# shield-ssr-display.net
KiCad netlist of a schematic drawn in EAGLE
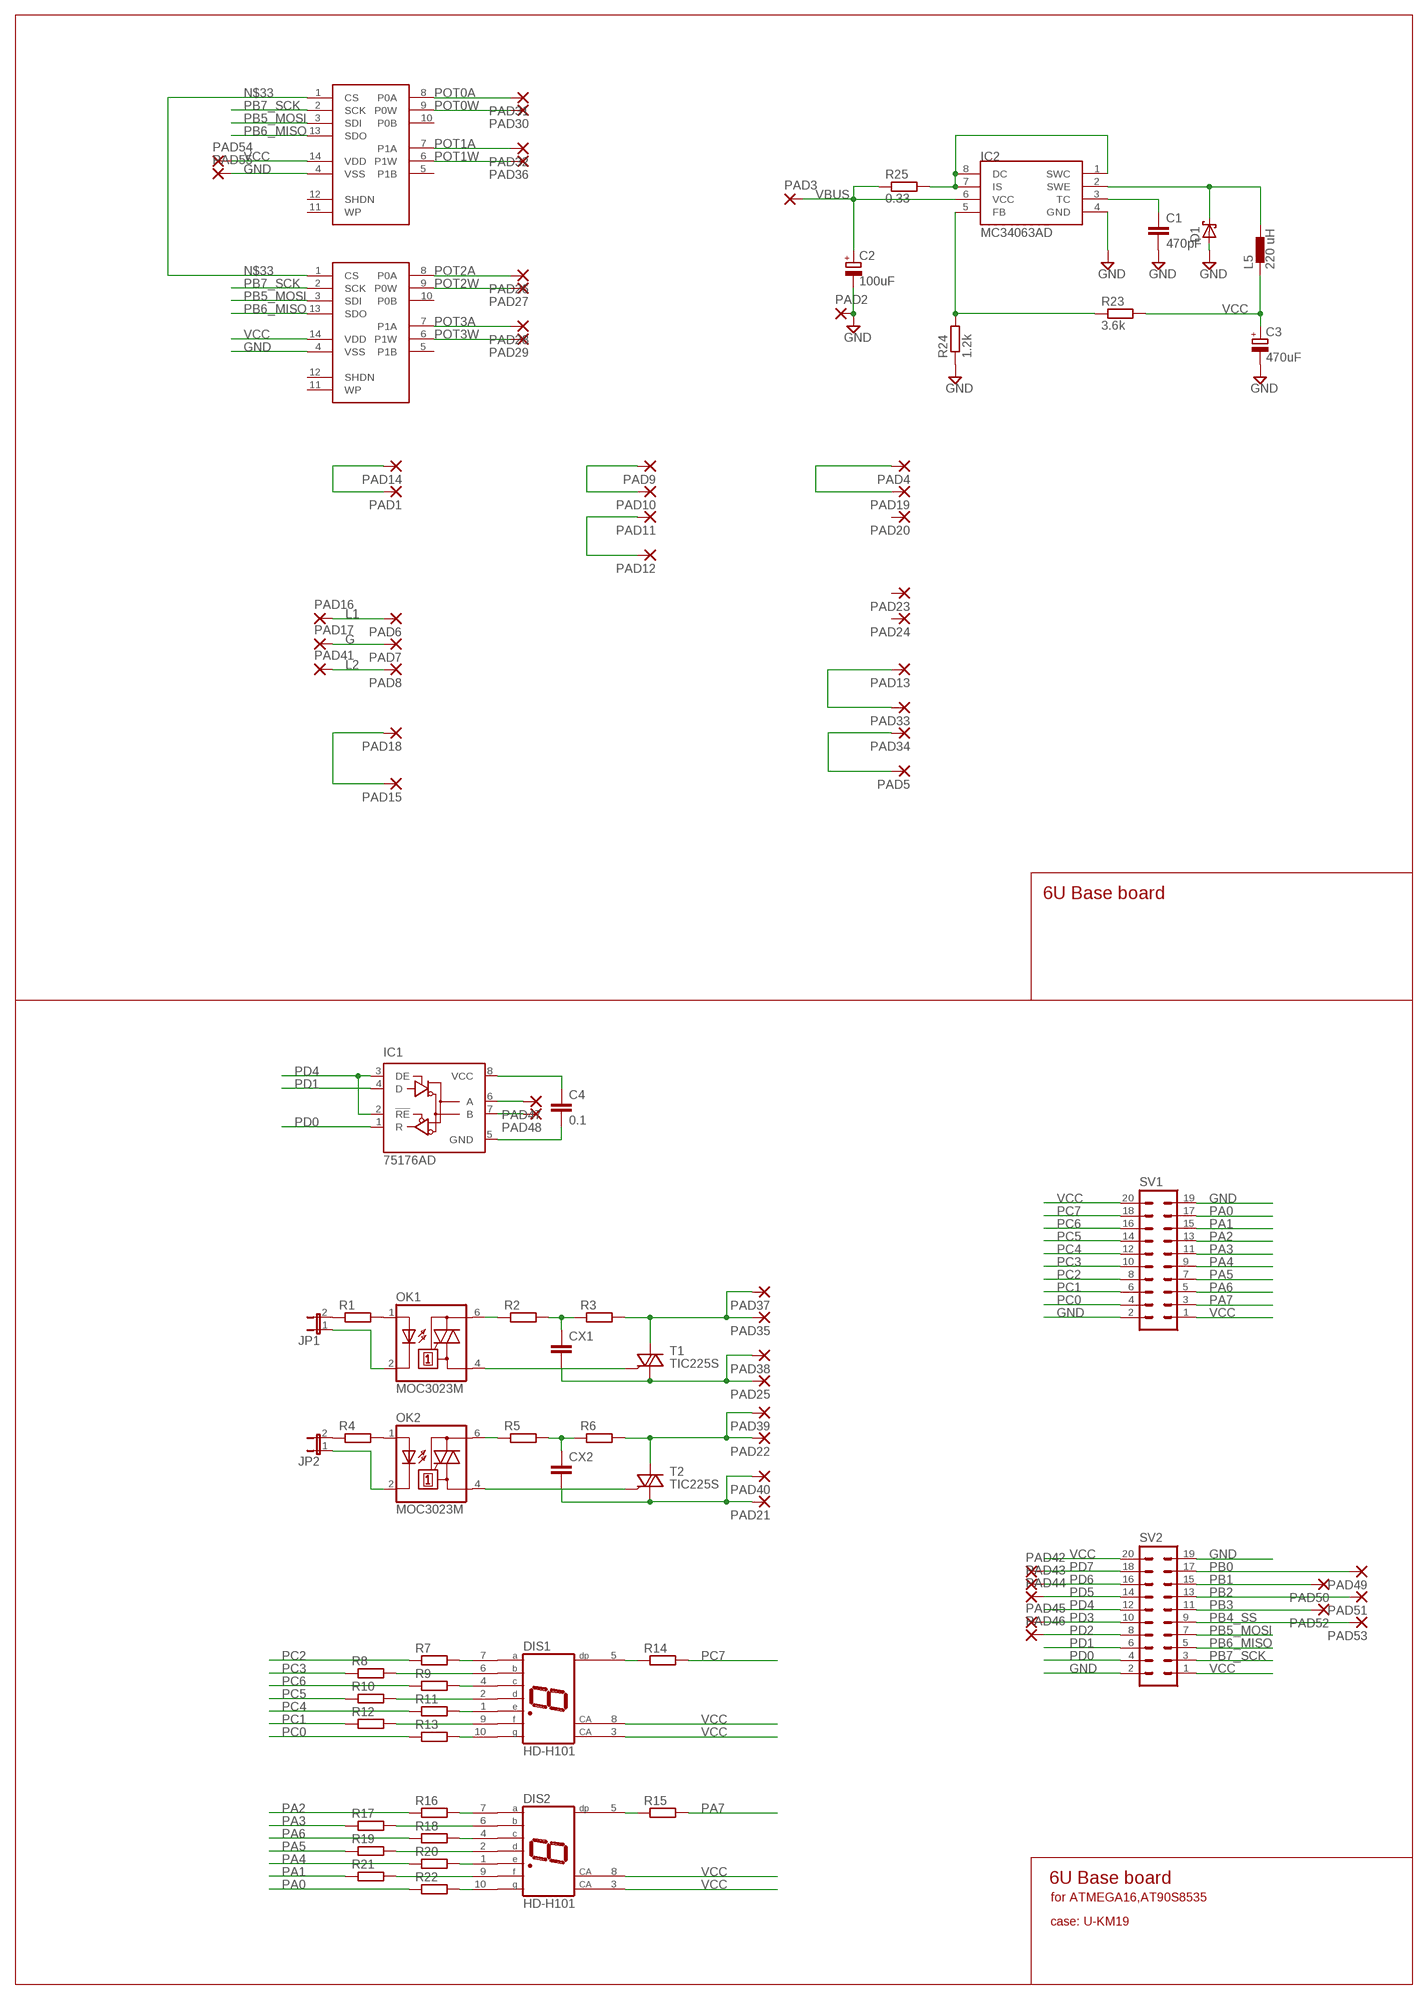
[diagram p0: schematic, sheet 1]

(export (version "E")
  (design (tool "Eeschema 10.0.6"))
  (components
    (comp (ref "C1")
      (value "470pF")
      (footprint "eagle-import:C0805")
      (libsource (lib "eagle-import") (part "C-EUC0805"))
    )
    (comp (ref "C2")
      (value "100uF")
      (footprint "eagle-import:E3,5-8")
      (libsource (lib "eagle-import") (part "CPOL-EUE3.5-8"))
    )
    (comp (ref "C3")
      (value "470uF")
      (footprint "eagle-import:E3,5-8")
      (libsource (lib "eagle-import") (part "CPOL-EUE3.5-8"))
    )
    (comp (ref "C4")
      (value "0.1")
      (footprint "eagle-import:C0805")
      (libsource (lib "eagle-import") (part "C-EUC0805"))
    )
    (comp (ref "CX1")
      (value "CXXC15B5")
      (footprint "eagle-import:XC15B5")
      (libsource (lib "eagle-import") (part "CXXC15B5"))
    )
    (comp (ref "CX2")
      (value "CXXC15B5")
      (footprint "eagle-import:XC15B5")
      (libsource (lib "eagle-import") (part "CXXC15B5"))
    )
    (comp (ref "D1")
      (value "SCHOTTKY-DIODESMD")
      (footprint "eagle-import:SMB")
      (libsource (lib "eagle-import") (part "SCHOTTKY-DIODESMD"))
    )
    (comp (ref "DIS1")
      (value "HD-H101")
      (footprint "eagle-import:HDSP-M")
      (libsource (lib "eagle-import") (part "HD-H101"))
    )
    (comp (ref "DIS2")
      (value "HD-H101")
      (footprint "eagle-import:HDSP-M")
      (libsource (lib "eagle-import") (part "HD-H101"))
    )
    (comp (ref "IC1")
      (value "75176AD")
      (footprint "eagle-import:D_R-PDSO-G8")
      (libsource (lib "eagle-import") (part "75176AD"))
    )
    (comp (ref "IC2")
      (value "MC34063AD")
      (footprint "eagle-import:SOIC8")
      (libsource (lib "eagle-import") (part "MC34063AD"))
    )
    (comp (ref "JP1")
      (value "JP1E")
      (footprint "eagle-import:JP1")
      (libsource (lib "eagle-import") (part "JP1E"))
    )
    (comp (ref "JP2")
      (value "JP1E")
      (footprint "eagle-import:JP1")
      (libsource (lib "eagle-import") (part "JP1E"))
    )
    (comp (ref "L5")
      (value "220 uH")
      (footprint "eagle-import:DR1030")
      (libsource (lib "eagle-import") (part "DR1030"))
    )
    (comp (ref "OK1")
      (value "MOC3023M")
      (footprint "eagle-import:DIL06")
      (fields (field (name "MF") "FAIRCHILD SEMICONDUCTOR") (field (name "MPN") "MOC3023-M"))
      (libsource (lib "eagle-import") (part "MOC30M23"))
    )
    (comp (ref "OK2")
      (value "MOC3023M")
      (footprint "eagle-import:DIL06")
      (fields (field (name "MF") "FAIRCHILD SEMICONDUCTOR") (field (name "MPN") "MOC3023-M"))
      (libsource (lib "eagle-import") (part "MOC30M23"))
    )
    (comp (ref "PAD1")
      (value "2,54/0,8")
      (footprint "eagle-import:2,54_0,8")
      (libsource (lib "eagle-import") (part "2,54/0,8"))
    )
    (comp (ref "PAD2")
      (value "2,54/0,8")
      (footprint "eagle-import:2,54_0,8")
      (libsource (lib "eagle-import") (part "2,54/0,8"))
    )
    (comp (ref "PAD3")
      (value "2,54/0,8")
      (footprint "eagle-import:2,54_0,8")
      (libsource (lib "eagle-import") (part "2,54/0,8"))
    )
    (comp (ref "PAD4")
      (value "2,54/0,8")
      (footprint "eagle-import:2,54_0,8")
      (libsource (lib "eagle-import") (part "2,54/0,8"))
    )
    (comp (ref "PAD5")
      (value "2,54/0,8")
      (footprint "eagle-import:2,54_0,8")
      (libsource (lib "eagle-import") (part "2,54/0,8"))
    )
    (comp (ref "PAD6")
      (value "2,54/0,8")
      (footprint "eagle-import:2,54_0,8")
      (libsource (lib "eagle-import") (part "2,54/0,8"))
    )
    (comp (ref "PAD7")
      (value "2,54/0,8")
      (footprint "eagle-import:2,54_0,8")
      (libsource (lib "eagle-import") (part "2,54/0,8"))
    )
    (comp (ref "PAD8")
      (value "2,54/0,8")
      (footprint "eagle-import:2,54_0,8")
      (libsource (lib "eagle-import") (part "2,54/0,8"))
    )
    (comp (ref "PAD9")
      (value "2,54/0,8")
      (footprint "eagle-import:2,54_0,8")
      (libsource (lib "eagle-import") (part "2,54/0,8"))
    )
    (comp (ref "PAD10")
      (value "2,54/0,8")
      (footprint "eagle-import:2,54_0,8")
      (libsource (lib "eagle-import") (part "2,54/0,8"))
    )
    (comp (ref "PAD11")
      (value "2,54/0,8")
      (footprint "eagle-import:2,54_0,8")
      (libsource (lib "eagle-import") (part "2,54/0,8"))
    )
    (comp (ref "PAD12")
      (value "2,54/0,8")
      (footprint "eagle-import:2,54_0,8")
      (libsource (lib "eagle-import") (part "2,54/0,8"))
    )
    (comp (ref "PAD13")
      (value "2,54/0,8")
      (footprint "eagle-import:2,54_0,8")
      (libsource (lib "eagle-import") (part "2,54/0,8"))
    )
    (comp (ref "PAD14")
      (value "2,54/0,8")
      (footprint "eagle-import:2,54_0,8")
      (libsource (lib "eagle-import") (part "2,54/0,8"))
    )
    (comp (ref "PAD15")
      (value "2,54/0,8")
      (footprint "eagle-import:2,54_0,8")
      (libsource (lib "eagle-import") (part "2,54/0,8"))
    )
    (comp (ref "PAD16")
      (value "2,54/0,8")
      (footprint "eagle-import:2,54_0,8")
      (libsource (lib "eagle-import") (part "2,54/0,8"))
    )
    (comp (ref "PAD17")
      (value "2,54/0,8")
      (footprint "eagle-import:2,54_0,8")
      (libsource (lib "eagle-import") (part "2,54/0,8"))
    )
    (comp (ref "PAD18")
      (value "2,54/0,8")
      (footprint "eagle-import:2,54_0,8")
      (libsource (lib "eagle-import") (part "2,54/0,8"))
    )
    (comp (ref "PAD19")
      (value "2,54/0,8")
      (footprint "eagle-import:2,54_0,8")
      (libsource (lib "eagle-import") (part "2,54/0,8"))
    )
    (comp (ref "PAD20")
      (value "2,54/0,8")
      (footprint "eagle-import:2,54_0,8")
      (libsource (lib "eagle-import") (part "2,54/0,8"))
    )
    (comp (ref "PAD21")
      (value "2,54/0,8")
      (footprint "eagle-import:2,54_0,8")
      (libsource (lib "eagle-import") (part "2,54/0,8"))
    )
    (comp (ref "PAD22")
      (value "2,54/0,8")
      (footprint "eagle-import:2,54_0,8")
      (libsource (lib "eagle-import") (part "2,54/0,8"))
    )
    (comp (ref "PAD23")
      (value "2,54/0,8")
      (footprint "eagle-import:2,54_0,8")
      (libsource (lib "eagle-import") (part "2,54/0,8"))
    )
    (comp (ref "PAD24")
      (value "2,54/0,8")
      (footprint "eagle-import:2,54_0,8")
      (libsource (lib "eagle-import") (part "2,54/0,8"))
    )
    (comp (ref "PAD25")
      (value "2,54/0,8")
      (footprint "eagle-import:2,54_0,8")
      (libsource (lib "eagle-import") (part "2,54/0,8"))
    )
    (comp (ref "PAD26")
      (value "2,54/0,8")
      (footprint "eagle-import:2,54_0,8")
      (libsource (lib "eagle-import") (part "2,54/0,8"))
    )
    (comp (ref "PAD27")
      (value "2,54/0,8")
      (footprint "eagle-import:2,54_0,8")
      (libsource (lib "eagle-import") (part "2,54/0,8"))
    )
    (comp (ref "PAD28")
      (value "2,54/0,8")
      (footprint "eagle-import:2,54_0,8")
      (libsource (lib "eagle-import") (part "2,54/0,8"))
    )
    (comp (ref "PAD29")
      (value "2,54/0,8")
      (footprint "eagle-import:2,54_0,8")
      (libsource (lib "eagle-import") (part "2,54/0,8"))
    )
    (comp (ref "PAD30")
      (value "2,54/0,8")
      (footprint "eagle-import:2,54_0,8")
      (libsource (lib "eagle-import") (part "2,54/0,8"))
    )
    (comp (ref "PAD31")
      (value "2,54/0,8")
      (footprint "eagle-import:2,54_0,8")
      (libsource (lib "eagle-import") (part "2,54/0,8"))
    )
    (comp (ref "PAD32")
      (value "2,54/0,8")
      (footprint "eagle-import:2,54_0,8")
      (libsource (lib "eagle-import") (part "2,54/0,8"))
    )
    (comp (ref "PAD33")
      (value "2,54/0,8")
      (footprint "eagle-import:2,54_0,8")
      (libsource (lib "eagle-import") (part "2,54/0,8"))
    )
    (comp (ref "PAD34")
      (value "2,54/0,8")
      (footprint "eagle-import:2,54_0,8")
      (libsource (lib "eagle-import") (part "2,54/0,8"))
    )
    (comp (ref "PAD35")
      (value "2,54/0,8")
      (footprint "eagle-import:2,54_0,8")
      (libsource (lib "eagle-import") (part "2,54/0,8"))
    )
    (comp (ref "PAD36")
      (value "2,54/0,8")
      (footprint "eagle-import:2,54_0,8")
      (libsource (lib "eagle-import") (part "2,54/0,8"))
    )
    (comp (ref "PAD37")
      (value "2,54/0,8")
      (footprint "eagle-import:2,54_0,8")
      (libsource (lib "eagle-import") (part "2,54/0,8"))
    )
    (comp (ref "PAD38")
      (value "2,54/0,8")
      (footprint "eagle-import:2,54_0,8")
      (libsource (lib "eagle-import") (part "2,54/0,8"))
    )
    (comp (ref "PAD39")
      (value "2,54/0,8")
      (footprint "eagle-import:2,54_0,8")
      (libsource (lib "eagle-import") (part "2,54/0,8"))
    )
    (comp (ref "PAD40")
      (value "2,54/0,8")
      (footprint "eagle-import:2,54_0,8")
      (libsource (lib "eagle-import") (part "2,54/0,8"))
    )
    (comp (ref "PAD41")
      (value "2,54/0,8")
      (footprint "eagle-import:2,54_0,8")
      (libsource (lib "eagle-import") (part "2,54/0,8"))
    )
    (comp (ref "PAD42")
      (value "1,6/0,8")
      (footprint "eagle-import:1,6_0,8")
      (libsource (lib "eagle-import") (part "1,6/0,8"))
    )
    (comp (ref "PAD43")
      (value "1,6/0,8")
      (footprint "eagle-import:1,6_0,8")
      (libsource (lib "eagle-import") (part "1,6/0,8"))
    )
    (comp (ref "PAD44")
      (value "1,6/0,8")
      (footprint "eagle-import:1,6_0,8")
      (libsource (lib "eagle-import") (part "1,6/0,8"))
    )
    (comp (ref "PAD45")
      (value "1,6/0,8")
      (footprint "eagle-import:1,6_0,8")
      (libsource (lib "eagle-import") (part "1,6/0,8"))
    )
    (comp (ref "PAD46")
      (value "1,6/0,8")
      (footprint "eagle-import:1,6_0,8")
      (libsource (lib "eagle-import") (part "1,6/0,8"))
    )
    (comp (ref "PAD47")
      (value "1,6/0,8")
      (footprint "eagle-import:1,6_0,8")
      (libsource (lib "eagle-import") (part "1,6/0,8"))
    )
    (comp (ref "PAD48")
      (value "1,6/0,8")
      (footprint "eagle-import:1,6_0,8")
      (libsource (lib "eagle-import") (part "1,6/0,8"))
    )
    (comp (ref "PAD49")
      (value "1,6/0,8")
      (footprint "eagle-import:1,6_0,8")
      (libsource (lib "eagle-import") (part "1,6/0,8"))
    )
    (comp (ref "PAD50")
      (value "1,6/0,8")
      (footprint "eagle-import:1,6_0,8")
      (libsource (lib "eagle-import") (part "1,6/0,8"))
    )
    (comp (ref "PAD51")
      (value "1,6/0,8")
      (footprint "eagle-import:1,6_0,8")
      (libsource (lib "eagle-import") (part "1,6/0,8"))
    )
    (comp (ref "PAD52")
      (value "1,6/0,8")
      (footprint "eagle-import:1,6_0,8")
      (libsource (lib "eagle-import") (part "1,6/0,8"))
    )
    (comp (ref "PAD53")
      (value "1,6/0,8")
      (footprint "eagle-import:1,6_0,8")
      (libsource (lib "eagle-import") (part "1,6/0,8"))
    )
    (comp (ref "PAD54")
      (value "1,6/0,8")
      (footprint "eagle-import:1,6_0,8")
      (libsource (lib "eagle-import") (part "1,6/0,8"))
    )
    (comp (ref "PAD55")
      (value "1,6/0,8")
      (footprint "eagle-import:1,6_0,8")
      (libsource (lib "eagle-import") (part "1,6/0,8"))
    )
    (comp (ref "R1")
      (value "R-EU_M0805")
      (footprint "eagle-import:M0805")
      (libsource (lib "eagle-import") (part "R-EU_M0805"))
    )
    (comp (ref "R2")
      (value "R-EU_R1206")
      (footprint "eagle-import:R1206")
      (libsource (lib "eagle-import") (part "R-EU_R1206"))
    )
    (comp (ref "R3")
      (value "R-EU_R1206")
      (footprint "eagle-import:R1206")
      (libsource (lib "eagle-import") (part "R-EU_R1206"))
    )
    (comp (ref "R4")
      (value "R-EU_M0805")
      (footprint "eagle-import:M0805")
      (libsource (lib "eagle-import") (part "R-EU_M0805"))
    )
    (comp (ref "R5")
      (value "R-EU_R1206")
      (footprint "eagle-import:R1206")
      (libsource (lib "eagle-import") (part "R-EU_R1206"))
    )
    (comp (ref "R6")
      (value "R-EU_R1206")
      (footprint "eagle-import:R1206")
      (libsource (lib "eagle-import") (part "R-EU_R1206"))
    )
    (comp (ref "R7")
      (value "R-EU_R0603")
      (footprint "eagle-import:R0603")
      (libsource (lib "eagle-import") (part "R-EU_R0603"))
    )
    (comp (ref "R8")
      (value "R-EU_R0603")
      (footprint "eagle-import:R0603")
      (libsource (lib "eagle-import") (part "R-EU_R0603"))
    )
    (comp (ref "R9")
      (value "R-EU_R0603")
      (footprint "eagle-import:R0603")
      (libsource (lib "eagle-import") (part "R-EU_R0603"))
    )
    (comp (ref "R10")
      (value "R-EU_R0603")
      (footprint "eagle-import:R0603")
      (libsource (lib "eagle-import") (part "R-EU_R0603"))
    )
    (comp (ref "R11")
      (value "R-EU_R0603")
      (footprint "eagle-import:R0603")
      (libsource (lib "eagle-import") (part "R-EU_R0603"))
    )
    (comp (ref "R12")
      (value "R-EU_R0603")
      (footprint "eagle-import:R0603")
      (libsource (lib "eagle-import") (part "R-EU_R0603"))
    )
    (comp (ref "R13")
      (value "R-EU_R0603")
      (footprint "eagle-import:R0603")
      (libsource (lib "eagle-import") (part "R-EU_R0603"))
    )
    (comp (ref "R14")
      (value "R-EU_R0603")
      (footprint "eagle-import:R0603")
      (libsource (lib "eagle-import") (part "R-EU_R0603"))
    )
    (comp (ref "R15")
      (value "R-EU_R0603")
      (footprint "eagle-import:R0603")
      (libsource (lib "eagle-import") (part "R-EU_R0603"))
    )
    (comp (ref "R16")
      (value "R-EU_R0603")
      (footprint "eagle-import:R0603")
      (libsource (lib "eagle-import") (part "R-EU_R0603"))
    )
    (comp (ref "R17")
      (value "R-EU_R0603")
      (footprint "eagle-import:R0603")
      (libsource (lib "eagle-import") (part "R-EU_R0603"))
    )
    (comp (ref "R18")
      (value "R-EU_R0603")
      (footprint "eagle-import:R0603")
      (libsource (lib "eagle-import") (part "R-EU_R0603"))
    )
    (comp (ref "R19")
      (value "R-EU_R0603")
      (footprint "eagle-import:R0603")
      (libsource (lib "eagle-import") (part "R-EU_R0603"))
    )
    (comp (ref "R20")
      (value "R-EU_R0603")
      (footprint "eagle-import:R0603")
      (libsource (lib "eagle-import") (part "R-EU_R0603"))
    )
    (comp (ref "R21")
      (value "R-EU_R0603")
      (footprint "eagle-import:R0603")
      (libsource (lib "eagle-import") (part "R-EU_R0603"))
    )
    (comp (ref "R22")
      (value "R-EU_R0603")
      (footprint "eagle-import:R0603")
      (libsource (lib "eagle-import") (part "R-EU_R0603"))
    )
    (comp (ref "R23")
      (value "3.6k")
      (footprint "eagle-import:R0805")
      (libsource (lib "eagle-import") (part "R-EU_R0805"))
    )
    (comp (ref "R24")
      (value "1.2k")
      (footprint "eagle-import:R0805")
      (libsource (lib "eagle-import") (part "R-EU_R0805"))
    )
    (comp (ref "R25")
      (value "0.33")
      (footprint "eagle-import:R1206")
      (libsource (lib "eagle-import") (part "R-EU_R1206"))
    )
    (comp (ref "SV1")
      (value "MA10-2")
      (footprint "eagle-import:MA10-2")
      (libsource (lib "eagle-import") (part "MA10-2"))
    )
    (comp (ref "SV2")
      (value "MA10-2")
      (footprint "eagle-import:MA10-2")
      (libsource (lib "eagle-import") (part "MA10-2"))
    )
    (comp (ref "T1")
      (value "TIC225S")
      (footprint "eagle-import:TO220DS")
      (libsource (lib "eagle-import") (part "TIC225S"))
    )
    (comp (ref "T2")
      (value "TIC225S")
      (footprint "eagle-import:TO220DS")
      (libsource (lib "eagle-import") (part "TIC225S"))
    )
    (comp (ref "U$1")
      (value "MCP4231-DIP")
      (footprint "eagle-import:DIL14")
      (libsource (lib "eagle-import") (part "MCP4231-DIP"))
    )
    (comp (ref "U$2")
      (value "MCP4231-DIP")
      (footprint "eagle-import:DIL14")
      (libsource (lib "eagle-import") (part "MCP4231-DIP"))
    )
  )
  (nets
    (net (code "1") (name "/G") (class "Default")
      (node (ref "PAD17") (pin "1") (pinfunction "P_1") (pintype "passive"))
      (node (ref "PAD7") (pin "1") (pinfunction "P_1") (pintype "passive"))
    )
    (net (code "2") (name "/L1") (class "Default")
      (node (ref "PAD16") (pin "1") (pinfunction "P_1") (pintype "passive"))
      (node (ref "PAD6") (pin "1") (pinfunction "P_1") (pintype "passive"))
    )
    (net (code "3") (name "/L2") (class "Default")
      (node (ref "PAD41") (pin "1") (pinfunction "P_1") (pintype "passive"))
      (node (ref "PAD8") (pin "1") (pinfunction "P_1") (pintype "passive"))
    )
    (net (code "4") (name "/N$33") (class "Default")
      (node (ref "U$1") (pin "1") (pinfunction "CS_1") (pintype "bidirectional"))
      (node (ref "U$2") (pin "1") (pinfunction "CS_1") (pintype "bidirectional"))
    )
    (net (code "5") (name "/PA0") (class "Default")
      (node (ref "R22") (pin "1") (pinfunction "1_1") (pintype "passive"))
      (node (ref "SV1") (pin "17") (pinfunction "17_17") (pintype "passive"))
    )
    (net (code "6") (name "/PA1") (class "Default")
      (node (ref "R21") (pin "1") (pinfunction "1_1") (pintype "passive"))
      (node (ref "SV1") (pin "15") (pinfunction "15_15") (pintype "passive"))
    )
    (net (code "7") (name "/PA2") (class "Default")
      (node (ref "R16") (pin "1") (pinfunction "1_1") (pintype "passive"))
      (node (ref "SV1") (pin "13") (pinfunction "13_13") (pintype "passive"))
    )
    (net (code "8") (name "/PA3") (class "Default")
      (node (ref "R17") (pin "1") (pinfunction "1_1") (pintype "passive"))
      (node (ref "SV1") (pin "11") (pinfunction "11_11") (pintype "passive"))
    )
    (net (code "9") (name "/PA4") (class "Default")
      (node (ref "R20") (pin "1") (pinfunction "1_1") (pintype "passive"))
      (node (ref "SV1") (pin "9") (pinfunction "9_9") (pintype "passive"))
    )
    (net (code "10") (name "/PA5") (class "Default")
      (node (ref "R19") (pin "1") (pinfunction "1_1") (pintype "passive"))
      (node (ref "SV1") (pin "7") (pinfunction "7_7") (pintype "passive"))
    )
    (net (code "11") (name "/PA6") (class "Default")
      (node (ref "R18") (pin "1") (pinfunction "1_1") (pintype "passive"))
      (node (ref "SV1") (pin "5") (pinfunction "5_5") (pintype "passive"))
    )
    (net (code "12") (name "/PA7") (class "Default")
      (node (ref "R15") (pin "2") (pinfunction "2_2") (pintype "passive"))
      (node (ref "SV1") (pin "3") (pinfunction "3_3") (pintype "passive"))
    )
    (net (code "13") (name "/PB0") (class "Default")
      (node (ref "PAD49") (pin "1") (pinfunction "P_1") (pintype "passive"))
      (node (ref "SV2") (pin "17") (pinfunction "17_17") (pintype "passive"))
    )
    (net (code "14") (name "/PB1") (class "Default")
      (node (ref "PAD50") (pin "1") (pinfunction "P_1") (pintype "passive"))
      (node (ref "SV2") (pin "15") (pinfunction "15_15") (pintype "passive"))
    )
    (net (code "15") (name "/PB2") (class "Default")
      (node (ref "PAD51") (pin "1") (pinfunction "P_1") (pintype "passive"))
      (node (ref "SV2") (pin "13") (pinfunction "13_13") (pintype "passive"))
    )
    (net (code "16") (name "/PB3") (class "Default")
      (node (ref "PAD52") (pin "1") (pinfunction "P_1") (pintype "passive"))
      (node (ref "SV2") (pin "11") (pinfunction "11_11") (pintype "passive"))
    )
    (net (code "17") (name "/PB4_SS") (class "Default")
      (node (ref "PAD53") (pin "1") (pinfunction "P_1") (pintype "passive"))
      (node (ref "SV2") (pin "9") (pinfunction "9_9") (pintype "passive"))
    )
    (net (code "18") (name "/PB5_MOSI") (class "Default")
      (node (ref "SV2") (pin "7") (pinfunction "7_7") (pintype "passive"))
      (node (ref "U$1") (pin "3") (pinfunction "SDI_3") (pintype "bidirectional"))
      (node (ref "U$2") (pin "3") (pinfunction "SDI_3") (pintype "bidirectional"))
    )
    (net (code "19") (name "/PB6_MISO") (class "Default")
      (node (ref "SV2") (pin "5") (pinfunction "5_5") (pintype "passive"))
      (node (ref "U$1") (pin "13") (pinfunction "SDO_13") (pintype "bidirectional"))
      (node (ref "U$2") (pin "13") (pinfunction "SDO_13") (pintype "bidirectional"))
    )
    (net (code "20") (name "/PB7_SCK") (class "Default")
      (node (ref "SV2") (pin "3") (pinfunction "3_3") (pintype "passive"))
      (node (ref "U$1") (pin "2") (pinfunction "SCK_2") (pintype "bidirectional"))
      (node (ref "U$2") (pin "2") (pinfunction "SCK_2") (pintype "bidirectional"))
    )
    (net (code "21") (name "/PC0") (class "Default")
      (node (ref "R13") (pin "1") (pinfunction "1_1") (pintype "passive"))
      (node (ref "SV1") (pin "4") (pinfunction "4_4") (pintype "passive"))
    )
    (net (code "22") (name "/PC1") (class "Default")
      (node (ref "R12") (pin "1") (pinfunction "1_1") (pintype "passive"))
      (node (ref "SV1") (pin "6") (pinfunction "6_6") (pintype "passive"))
    )
    (net (code "23") (name "/PC2") (class "Default")
      (node (ref "R7") (pin "1") (pinfunction "1_1") (pintype "passive"))
      (node (ref "SV1") (pin "8") (pinfunction "8_8") (pintype "passive"))
    )
    (net (code "24") (name "/PC3") (class "Default")
      (node (ref "R8") (pin "1") (pinfunction "1_1") (pintype "passive"))
      (node (ref "SV1") (pin "10") (pinfunction "10_10") (pintype "passive"))
    )
    (net (code "25") (name "/PC4") (class "Default")
      (node (ref "R11") (pin "1") (pinfunction "1_1") (pintype "passive"))
      (node (ref "SV1") (pin "12") (pinfunction "12_12") (pintype "passive"))
    )
    (net (code "26") (name "/PC5") (class "Default")
      (node (ref "R10") (pin "1") (pinfunction "1_1") (pintype "passive"))
      (node (ref "SV1") (pin "14") (pinfunction "14_14") (pintype "passive"))
    )
    (net (code "27") (name "/PC6") (class "Default")
      (node (ref "R9") (pin "1") (pinfunction "1_1") (pintype "passive"))
      (node (ref "SV1") (pin "16") (pinfunction "16_16") (pintype "passive"))
    )
    (net (code "28") (name "/PC7") (class "Default")
      (node (ref "R14") (pin "2") (pinfunction "2_2") (pintype "passive"))
      (node (ref "SV1") (pin "18") (pinfunction "18_18") (pintype "passive"))
    )
    (net (code "29") (name "/PD0") (class "Default")
      (node (ref "IC1") (pin "1") (pinfunction "R_1") (pintype "input"))
      (node (ref "SV2") (pin "4") (pinfunction "4_4") (pintype "passive"))
    )
    (net (code "30") (name "/PD1") (class "Default")
      (node (ref "IC1") (pin "4") (pinfunction "D_4") (pintype "input"))
      (node (ref "SV2") (pin "6") (pinfunction "6_6") (pintype "passive"))
    )
    (net (code "31") (name "/PD2") (class "Default")
      (node (ref "PAD46") (pin "1") (pinfunction "P_1") (pintype "passive"))
      (node (ref "SV2") (pin "8") (pinfunction "8_8") (pintype "passive"))
    )
    (net (code "32") (name "/PD3") (class "Default")
      (node (ref "PAD45") (pin "1") (pinfunction "P_1") (pintype "passive"))
      (node (ref "SV2") (pin "10") (pinfunction "10_10") (pintype "passive"))
    )
    (net (code "33") (name "/PD4") (class "Default")
      (node (ref "IC1") (pin "2") (pinfunction "~{RE}_2") (pintype "input"))
      (node (ref "IC1") (pin "3") (pinfunction "DE_3") (pintype "input"))
      (node (ref "SV2") (pin "12") (pinfunction "12_12") (pintype "passive"))
    )
    (net (code "34") (name "/PD5") (class "Default")
      (node (ref "PAD44") (pin "1") (pinfunction "P_1") (pintype "passive"))
      (node (ref "SV2") (pin "14") (pinfunction "14_14") (pintype "passive"))
    )
    (net (code "35") (name "/PD6") (class "Default")
      (node (ref "PAD43") (pin "1") (pinfunction "P_1") (pintype "passive"))
      (node (ref "SV2") (pin "16") (pinfunction "16_16") (pintype "passive"))
    )
    (net (code "36") (name "/PD7") (class "Default")
      (node (ref "PAD42") (pin "1") (pinfunction "P_1") (pintype "passive"))
      (node (ref "SV2") (pin "18") (pinfunction "18_18") (pintype "passive"))
    )
    (net (code "37") (name "/POT0A") (class "Default")
      (node (ref "PAD31") (pin "1") (pinfunction "P_1") (pintype "passive"))
      (node (ref "U$1") (pin "8") (pinfunction "P0A_8") (pintype "bidirectional"))
    )
    (net (code "38") (name "/POT0W") (class "Default")
      (node (ref "PAD30") (pin "1") (pinfunction "P_1") (pintype "passive"))
      (node (ref "U$1") (pin "9") (pinfunction "P0W_9") (pintype "bidirectional"))
    )
    (net (code "39") (name "/POT1A") (class "Default")
      (node (ref "PAD32") (pin "1") (pinfunction "P_1") (pintype "passive"))
      (node (ref "U$1") (pin "7") (pinfunction "P1A_7") (pintype "bidirectional"))
    )
    (net (code "40") (name "/POT1W") (class "Default")
      (node (ref "PAD36") (pin "1") (pinfunction "P_1") (pintype "passive"))
      (node (ref "U$1") (pin "6") (pinfunction "P1W_6") (pintype "bidirectional"))
    )
    (net (code "41") (name "/POT2A") (class "Default")
      (node (ref "PAD26") (pin "1") (pinfunction "P_1") (pintype "passive"))
      (node (ref "U$2") (pin "8") (pinfunction "P0A_8") (pintype "bidirectional"))
    )
    (net (code "42") (name "/POT2W") (class "Default")
      (node (ref "PAD27") (pin "1") (pinfunction "P_1") (pintype "passive"))
      (node (ref "U$2") (pin "9") (pinfunction "P0W_9") (pintype "bidirectional"))
    )
    (net (code "43") (name "/POT3A") (class "Default")
      (node (ref "PAD28") (pin "1") (pinfunction "P_1") (pintype "passive"))
      (node (ref "U$2") (pin "7") (pinfunction "P1A_7") (pintype "bidirectional"))
    )
    (net (code "44") (name "/POT3W") (class "Default")
      (node (ref "PAD29") (pin "1") (pinfunction "P_1") (pintype "passive"))
      (node (ref "U$2") (pin "6") (pinfunction "P1W_6") (pintype "bidirectional"))
    )
    (net (code "45") (name "/VBUS") (class "Default")
      (node (ref "C2") (pin "+") (pinfunction "+_+") (pintype "passive"))
      (node (ref "IC2") (pin "6") (pinfunction "VCC_6") (pintype "passive"))
      (node (ref "PAD3") (pin "1") (pinfunction "P_1") (pintype "passive"))
      (node (ref "R25") (pin "1") (pinfunction "1_1") (pintype "passive"))
    )
    (net (code "46") (name "/VCC") (class "Default")
      (node (ref "C3") (pin "+") (pinfunction "+_+") (pintype "passive"))
      (node (ref "C4") (pin "1") (pinfunction "1_1") (pintype "passive"))
      (node (ref "DIS1") (pin "3") (pinfunction "CA_3") (pintype "passive"))
      (node (ref "DIS1") (pin "8") (pinfunction "CA_8") (pintype "passive"))
      (node (ref "DIS2") (pin "3") (pinfunction "CA_3") (pintype "passive"))
      (node (ref "DIS2") (pin "8") (pinfunction "CA_8") (pintype "passive"))
      (node (ref "IC1") (pin "8") (pinfunction "VCC_8") (pintype "power_in"))
      (node (ref "L5") (pin "1") (pinfunction "1_1") (pintype "passive"))
      (node (ref "PAD34") (pin "1") (pinfunction "P_1") (pintype "passive"))
      (node (ref "PAD5") (pin "1") (pinfunction "P_1") (pintype "passive"))
      (node (ref "PAD54") (pin "1") (pinfunction "P_1") (pintype "passive"))
      (node (ref "R23") (pin "2") (pinfunction "2_2") (pintype "passive"))
      (node (ref "SV1") (pin "1") (pinfunction "1_1") (pintype "passive"))
      (node (ref "SV1") (pin "20") (pinfunction "20_20") (pintype "passive"))
      (node (ref "SV2") (pin "1") (pinfunction "1_1") (pintype "passive"))
      (node (ref "SV2") (pin "20") (pinfunction "20_20") (pintype "passive"))
      (node (ref "U$1") (pin "14") (pinfunction "VDD_14") (pintype "power_in"))
      (node (ref "U$2") (pin "14") (pinfunction "VDD_14") (pintype "power_in"))
    )
    (net (code "47") (name "GND") (class "Default")
      (node (ref "C1") (pin "2") (pinfunction "2_2") (pintype "passive"))
      (node (ref "C2") (pin "-") (pinfunction "-_-") (pintype "passive"))
      (node (ref "C3") (pin "-") (pinfunction "-_-") (pintype "passive"))
      (node (ref "C4") (pin "2") (pinfunction "2_2") (pintype "passive"))
      (node (ref "D1") (pin "A") (pinfunction "A_A") (pintype "passive"))
      (node (ref "IC1") (pin "5") (pinfunction "GND_5") (pintype "power_in"))
      (node (ref "IC2") (pin "4") (pinfunction "GND_4") (pintype "passive"))
      (node (ref "PAD19") (pin "1") (pinfunction "P_1") (pintype "passive"))
      (node (ref "PAD2") (pin "1") (pinfunction "P_1") (pintype "passive"))
      (node (ref "PAD4") (pin "1") (pinfunction "P_1") (pintype "passive"))
      (node (ref "PAD55") (pin "1") (pinfunction "P_1") (pintype "passive"))
      (node (ref "R24") (pin "1") (pinfunction "1_1") (pintype "passive"))
      (node (ref "SV1") (pin "19") (pinfunction "19_19") (pintype "passive"))
      (node (ref "SV1") (pin "2") (pinfunction "2_2") (pintype "passive"))
      (node (ref "SV2") (pin "19") (pinfunction "19_19") (pintype "passive"))
      (node (ref "SV2") (pin "2") (pinfunction "2_2") (pintype "passive"))
      (node (ref "U$1") (pin "4") (pinfunction "VSS_4") (pintype "power_in"))
      (node (ref "U$2") (pin "4") (pinfunction "VSS_4") (pintype "power_in"))
    )
    (net (code "48") (name "Net-(CX1-Pad1)") (class "Default")
      (node (ref "CX1") (pin "1") (pinfunction "1_1") (pintype "passive"))
      (node (ref "R2") (pin "2") (pinfunction "2_2") (pintype "passive"))
      (node (ref "R3") (pin "1") (pinfunction "1_1") (pintype "passive"))
    )
    (net (code "49") (name "Net-(CX2-Pad1)") (class "Default")
      (node (ref "CX2") (pin "1") (pinfunction "1_1") (pintype "passive"))
      (node (ref "R5") (pin "2") (pinfunction "2_2") (pintype "passive"))
      (node (ref "R6") (pin "1") (pinfunction "1_1") (pintype "passive"))
    )
    (net (code "50") (name "Net-(DIS1-A)") (class "Default")
      (node (ref "DIS1") (pin "7") (pinfunction "A_7") (pintype "passive"))
      (node (ref "R7") (pin "2") (pinfunction "2_2") (pintype "passive"))
    )
    (net (code "51") (name "Net-(DIS1-B)") (class "Default")
      (node (ref "DIS1") (pin "6") (pinfunction "B_6") (pintype "passive"))
      (node (ref "R8") (pin "2") (pinfunction "2_2") (pintype "passive"))
    )
    (net (code "52") (name "Net-(DIS1-C)") (class "Default")
      (node (ref "DIS1") (pin "4") (pinfunction "C_4") (pintype "passive"))
      (node (ref "R9") (pin "2") (pinfunction "2_2") (pintype "passive"))
    )
    (net (code "53") (name "Net-(DIS1-D)") (class "Default")
      (node (ref "DIS1") (pin "2") (pinfunction "D_2") (pintype "passive"))
      (node (ref "R10") (pin "2") (pinfunction "2_2") (pintype "passive"))
    )
    (net (code "54") (name "Net-(DIS1-DP)") (class "Default")
      (node (ref "DIS1") (pin "5") (pinfunction "DP_5") (pintype "passive"))
      (node (ref "R14") (pin "1") (pinfunction "1_1") (pintype "passive"))
    )
    (net (code "55") (name "Net-(DIS1-E)") (class "Default")
      (node (ref "DIS1") (pin "1") (pinfunction "E_1") (pintype "passive"))
      (node (ref "R11") (pin "2") (pinfunction "2_2") (pintype "passive"))
    )
    (net (code "56") (name "Net-(DIS1-F)") (class "Default")
      (node (ref "DIS1") (pin "9") (pinfunction "F_9") (pintype "passive"))
      (node (ref "R12") (pin "2") (pinfunction "2_2") (pintype "passive"))
    )
    (net (code "57") (name "Net-(DIS1-G)") (class "Default")
      (node (ref "DIS1") (pin "10") (pinfunction "G_10") (pintype "passive"))
      (node (ref "R13") (pin "2") (pinfunction "2_2") (pintype "passive"))
    )
    (net (code "58") (name "Net-(DIS2-A)") (class "Default")
      (node (ref "DIS2") (pin "7") (pinfunction "A_7") (pintype "passive"))
      (node (ref "R16") (pin "2") (pinfunction "2_2") (pintype "passive"))
    )
    (net (code "59") (name "Net-(DIS2-B)") (class "Default")
      (node (ref "DIS2") (pin "6") (pinfunction "B_6") (pintype "passive"))
      (node (ref "R17") (pin "2") (pinfunction "2_2") (pintype "passive"))
    )
    (net (code "60") (name "Net-(DIS2-C)") (class "Default")
      (node (ref "DIS2") (pin "4") (pinfunction "C_4") (pintype "passive"))
      (node (ref "R18") (pin "2") (pinfunction "2_2") (pintype "passive"))
    )
    (net (code "61") (name "Net-(DIS2-D)") (class "Default")
      (node (ref "DIS2") (pin "2") (pinfunction "D_2") (pintype "passive"))
      (node (ref "R19") (pin "2") (pinfunction "2_2") (pintype "passive"))
    )
    (net (code "62") (name "Net-(DIS2-DP)") (class "Default")
      (node (ref "DIS2") (pin "5") (pinfunction "DP_5") (pintype "passive"))
      (node (ref "R15") (pin "1") (pinfunction "1_1") (pintype "passive"))
    )
    (net (code "63") (name "Net-(DIS2-E)") (class "Default")
      (node (ref "DIS2") (pin "1") (pinfunction "E_1") (pintype "passive"))
      (node (ref "R20") (pin "2") (pinfunction "2_2") (pintype "passive"))
    )
    (net (code "64") (name "Net-(DIS2-F)") (class "Default")
      (node (ref "DIS2") (pin "9") (pinfunction "F_9") (pintype "passive"))
      (node (ref "R21") (pin "2") (pinfunction "2_2") (pintype "passive"))
    )
    (net (code "65") (name "Net-(DIS2-G)") (class "Default")
      (node (ref "DIS2") (pin "10") (pinfunction "G_10") (pintype "passive"))
      (node (ref "R22") (pin "2") (pinfunction "2_2") (pintype "passive"))
    )
    (net (code "66") (name "Net-(IC1-A)") (class "Default")
      (node (ref "IC1") (pin "6") (pinfunction "A_6") (pintype "output"))
      (node (ref "PAD47") (pin "1") (pinfunction "P_1") (pintype "passive"))
    )
    (net (code "67") (name "Net-(IC1-B)") (class "Default")
      (node (ref "IC1") (pin "7") (pinfunction "B_7") (pintype "output"))
      (node (ref "PAD48") (pin "1") (pinfunction "P_1") (pintype "passive"))
    )
    (net (code "68") (name "Net-(IC2-DC)") (class "Default")
      (node (ref "IC2") (pin "1") (pinfunction "SWC_1") (pintype "passive"))
      (node (ref "IC2") (pin "7") (pinfunction "IS_7") (pintype "passive"))
      (node (ref "IC2") (pin "8") (pinfunction "DC_8") (pintype "passive"))
      (node (ref "R25") (pin "2") (pinfunction "2_2") (pintype "passive"))
    )
    (net (code "69") (name "Net-(IC2-FB)") (class "Default")
      (node (ref "IC2") (pin "5") (pinfunction "FB_5") (pintype "passive"))
      (node (ref "R23") (pin "1") (pinfunction "1_1") (pintype "passive"))
      (node (ref "R24") (pin "2") (pinfunction "2_2") (pintype "passive"))
    )
    (net (code "70") (name "Net-(IC2-SWE)") (class "Default")
      (node (ref "D1") (pin "C") (pinfunction "C_C") (pintype "passive"))
      (node (ref "IC2") (pin "2") (pinfunction "SWE_2") (pintype "passive"))
      (node (ref "L5") (pin "2") (pinfunction "2_2") (pintype "passive"))
    )
    (net (code "71") (name "Net-(IC2-TC)") (class "Default")
      (node (ref "C1") (pin "1") (pinfunction "1_1") (pintype "passive"))
      (node (ref "IC2") (pin "3") (pinfunction "TC_3") (pintype "passive"))
    )
    (net (code "72") (name "Net-(JP1-Pad2)") (class "Default")
      (node (ref "JP1") (pin "2") (pinfunction "2_2") (pintype "passive"))
      (node (ref "R1") (pin "1") (pinfunction "1_1") (pintype "passive"))
    )
    (net (code "73") (name "Net-(JP2-Pad2)") (class "Default")
      (node (ref "JP2") (pin "2") (pinfunction "2_2") (pintype "passive"))
      (node (ref "R4") (pin "1") (pinfunction "1_1") (pintype "passive"))
    )
    (net (code "74") (name "Net-(OK1-A)") (class "Default")
      (node (ref "OK1") (pin "1") (pinfunction "A_1") (pintype "passive"))
      (node (ref "R1") (pin "2") (pinfunction "2_2") (pintype "passive"))
    )
    (net (code "75") (name "Net-(OK1-A1)") (class "Default")
      (node (ref "OK1") (pin "4") (pinfunction "A1_4") (pintype "passive"))
      (node (ref "T1") (pin "G") (pinfunction "G_G") (pintype "passive"))
    )
    (net (code "76") (name "Net-(OK1-A2)") (class "Default")
      (node (ref "OK1") (pin "6") (pinfunction "A2_6") (pintype "passive"))
      (node (ref "R2") (pin "1") (pinfunction "1_1") (pintype "passive"))
    )
    (net (code "77") (name "Net-(OK1-C)") (class "Default")
      (node (ref "JP1") (pin "1") (pinfunction "1_1") (pintype "passive"))
      (node (ref "OK1") (pin "2") (pinfunction "C_2") (pintype "passive"))
    )
    (net (code "78") (name "Net-(OK2-A)") (class "Default")
      (node (ref "OK2") (pin "1") (pinfunction "A_1") (pintype "passive"))
      (node (ref "R4") (pin "2") (pinfunction "2_2") (pintype "passive"))
    )
    (net (code "79") (name "Net-(OK2-A1)") (class "Default")
      (node (ref "OK2") (pin "4") (pinfunction "A1_4") (pintype "passive"))
      (node (ref "T2") (pin "G") (pinfunction "G_G") (pintype "passive"))
    )
    (net (code "80") (name "Net-(OK2-A2)") (class "Default")
      (node (ref "OK2") (pin "6") (pinfunction "A2_6") (pintype "passive"))
      (node (ref "R5") (pin "1") (pinfunction "1_1") (pintype "passive"))
    )
    (net (code "81") (name "Net-(OK2-C)") (class "Default")
      (node (ref "JP2") (pin "1") (pinfunction "1_1") (pintype "passive"))
      (node (ref "OK2") (pin "2") (pinfunction "C_2") (pintype "passive"))
    )
    (net (code "82") (name "Net-(PAD1-P)") (class "Default")
      (node (ref "PAD1") (pin "1") (pinfunction "P_1") (pintype "passive"))
      (node (ref "PAD14") (pin "1") (pinfunction "P_1") (pintype "passive"))
    )
    (net (code "83") (name "Net-(PAD10-P)") (class "Default")
      (node (ref "PAD10") (pin "1") (pinfunction "P_1") (pintype "passive"))
      (node (ref "PAD9") (pin "1") (pinfunction "P_1") (pintype "passive"))
    )
    (net (code "84") (name "Net-(PAD11-P)") (class "Default")
      (node (ref "PAD11") (pin "1") (pinfunction "P_1") (pintype "passive"))
      (node (ref "PAD12") (pin "1") (pinfunction "P_1") (pintype "passive"))
    )
    (net (code "85") (name "Net-(PAD13-P)") (class "Default")
      (node (ref "PAD13") (pin "1") (pinfunction "P_1") (pintype "passive"))
      (node (ref "PAD33") (pin "1") (pinfunction "P_1") (pintype "passive"))
    )
    (net (code "86") (name "Net-(PAD15-P)") (class "Default")
      (node (ref "PAD15") (pin "1") (pinfunction "P_1") (pintype "passive"))
      (node (ref "PAD18") (pin "1") (pinfunction "P_1") (pintype "passive"))
    )
    (net (code "87") (name "Net-(PAD21-P)") (class "Default")
      (node (ref "CX2") (pin "2") (pinfunction "2_2") (pintype "passive"))
      (node (ref "PAD21") (pin "1") (pinfunction "P_1") (pintype "passive"))
      (node (ref "PAD40") (pin "1") (pinfunction "P_1") (pintype "passive"))
      (node (ref "T2") (pin "A1") (pinfunction "A1_A1") (pintype "passive"))
    )
    (net (code "88") (name "Net-(PAD22-P)") (class "Default")
      (node (ref "PAD22") (pin "1") (pinfunction "P_1") (pintype "passive"))
      (node (ref "PAD39") (pin "1") (pinfunction "P_1") (pintype "passive"))
      (node (ref "R6") (pin "2") (pinfunction "2_2") (pintype "passive"))
      (node (ref "T2") (pin "A2") (pinfunction "A2_A2") (pintype "passive"))
    )
    (net (code "89") (name "Net-(PAD25-P)") (class "Default")
      (node (ref "CX1") (pin "2") (pinfunction "2_2") (pintype "passive"))
      (node (ref "PAD25") (pin "1") (pinfunction "P_1") (pintype "passive"))
      (node (ref "PAD38") (pin "1") (pinfunction "P_1") (pintype "passive"))
      (node (ref "T1") (pin "A1") (pinfunction "A1_A1") (pintype "passive"))
    )
    (net (code "90") (name "Net-(PAD35-P)") (class "Default")
      (node (ref "PAD35") (pin "1") (pinfunction "P_1") (pintype "passive"))
      (node (ref "PAD37") (pin "1") (pinfunction "P_1") (pintype "passive"))
      (node (ref "R3") (pin "2") (pinfunction "2_2") (pintype "passive"))
      (node (ref "T1") (pin "A2") (pinfunction "A2_A2") (pintype "passive"))
    )
    (net (code "91") (name "unconnected-(PAD20-P-Pad1)") (class "Default")
      (node (ref "PAD20") (pin "1") (pinfunction "P_1") (pintype "passive"))
    )
    (net (code "92") (name "unconnected-(PAD23-P-Pad1)") (class "Default")
      (node (ref "PAD23") (pin "1") (pinfunction "P_1") (pintype "passive"))
    )
    (net (code "93") (name "unconnected-(PAD24-P-Pad1)") (class "Default")
      (node (ref "PAD24") (pin "1") (pinfunction "P_1") (pintype "passive"))
    )
    (net (code "94") (name "unconnected-(U$1-P0B-Pad10)") (class "Default")
      (node (ref "U$1") (pin "10") (pinfunction "P0B_10") (pintype "bidirectional"))
    )
    (net (code "95") (name "unconnected-(U$1-P1B-Pad5)") (class "Default")
      (node (ref "U$1") (pin "5") (pinfunction "P1B_5") (pintype "bidirectional"))
    )
    (net (code "96") (name "unconnected-(U$1-SHDN-Pad12)") (class "Default")
      (node (ref "U$1") (pin "12") (pinfunction "SHDN_12") (pintype "input"))
    )
    (net (code "97") (name "unconnected-(U$1-WP-Pad11)") (class "Default")
      (node (ref "U$1") (pin "11") (pinfunction "WP_11") (pintype "input"))
    )
    (net (code "98") (name "unconnected-(U$2-P0B-Pad10)") (class "Default")
      (node (ref "U$2") (pin "10") (pinfunction "P0B_10") (pintype "bidirectional"))
    )
    (net (code "99") (name "unconnected-(U$2-P1B-Pad5)") (class "Default")
      (node (ref "U$2") (pin "5") (pinfunction "P1B_5") (pintype "bidirectional"))
    )
    (net (code "100") (name "unconnected-(U$2-SHDN-Pad12)") (class "Default")
      (node (ref "U$2") (pin "12") (pinfunction "SHDN_12") (pintype "input"))
    )
    (net (code "101") (name "unconnected-(U$2-WP-Pad11)") (class "Default")
      (node (ref "U$2") (pin "11") (pinfunction "WP_11") (pintype "input"))
    )
  )
)
